# Sheet1.net
KiCad netlist of a schematic drawn in Altium Designer
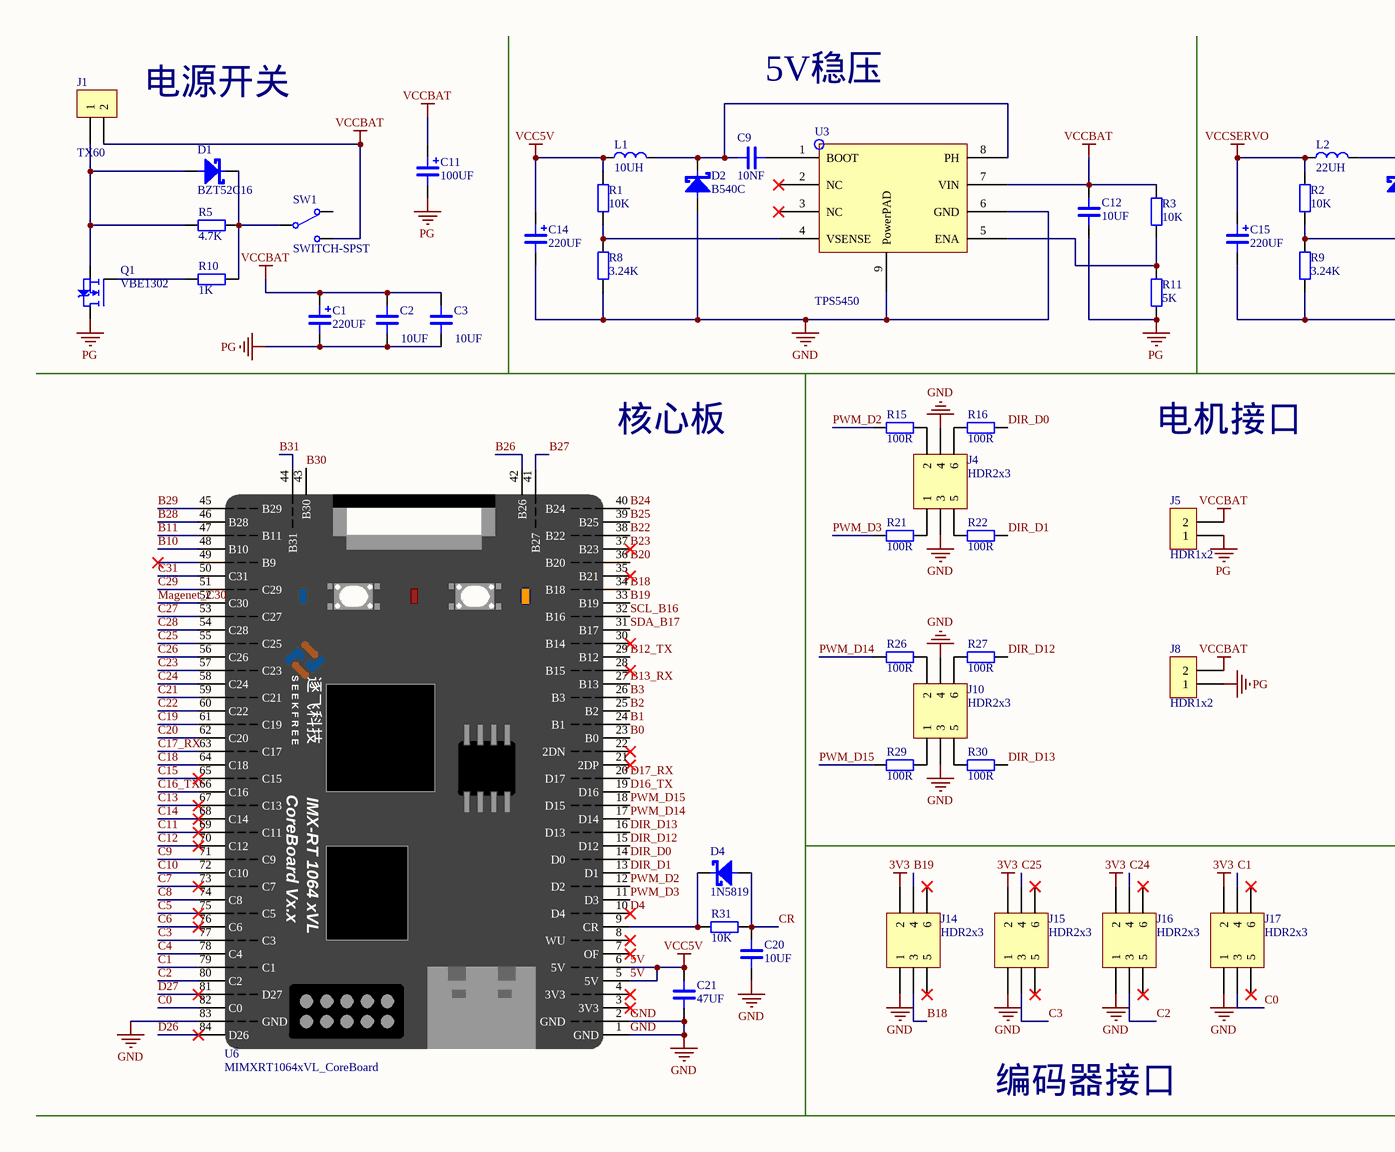
[diagram p0: Sheet1.SchDoc, left]
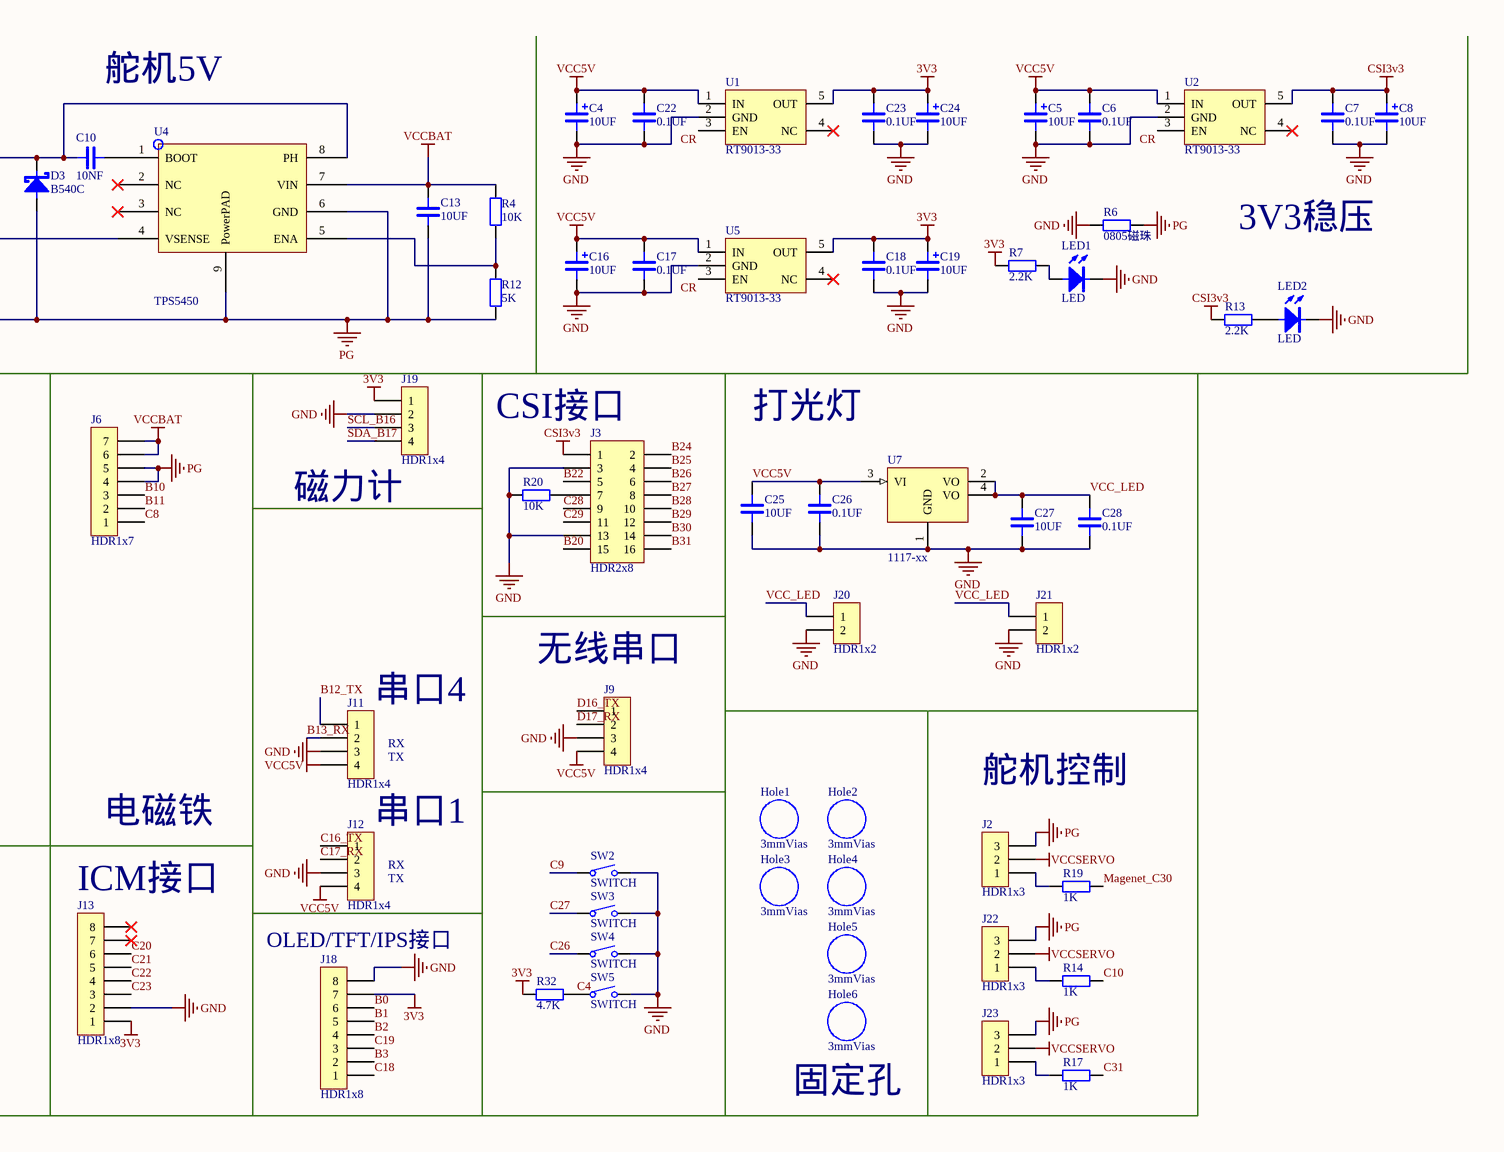
[diagram p1: Sheet1.SchDoc, right]

(export (version "E")
  (design (tool "Eeschema 10.0.6"))
  (components
    (comp (ref "C1")
      (value "220UF")
      (footprint "DIP-EC3.5X8X11.5")
      (description "Tantalum Capacitor")
      (libsource (lib "General") (part "CAP-TANTALUM"))
    )
    (comp (ref "C2")
      (value "10UF")
      (footprint "0603")
      (description "Capacitor")
      (libsource (lib "General") (part "CAP"))
    )
    (comp (ref "C3")
      (value "10UF")
      (footprint "0603")
      (description "Capacitor")
      (libsource (lib "General") (part "CAP"))
    )
    (comp (ref "C4")
      (value "10UF")
      (footprint "106")
      (description "Tantalum Capacitor")
      (libsource (lib "General") (part "CAP-TANTALUM"))
    )
    (comp (ref "C5")
      (value "10UF")
      (footprint "106")
      (description "Tantalum Capacitor")
      (libsource (lib "General") (part "CAP-TANTALUM"))
    )
    (comp (ref "C6")
      (value "0.1UF")
      (footprint "0603")
      (description "Capacitor")
      (libsource (lib "General") (part "CAP"))
    )
    (comp (ref "C7")
      (value "0.1UF")
      (footprint "0603")
      (description "Capacitor")
      (libsource (lib "General") (part "CAP"))
    )
    (comp (ref "C8")
      (value "10UF")
      (footprint "106")
      (description "Tantalum Capacitor")
      (libsource (lib "General") (part "CAP-TANTALUM"))
    )
    (comp (ref "C9")
      (value "10NF")
      (footprint "0603")
      (description "Capacitor")
      (libsource (lib "General") (part "CAP"))
    )
    (comp (ref "C10")
      (value "10NF")
      (footprint "0603")
      (description "Capacitor")
      (libsource (lib "General") (part "CAP"))
    )
    (comp (ref "C11")
      (value "100UF")
      (footprint "DIP-EC2.5X6.3X11.2")
      (description "Tantalum Capacitor")
      (libsource (lib "General") (part "CAP-TANTALUM"))
    )
    (comp (ref "C12")
      (value "10UF")
      (footprint "0603")
      (description "Capacitor")
      (libsource (lib "General") (part "CAP"))
    )
    (comp (ref "C13")
      (value "10UF")
      (footprint "0603")
      (description "Capacitor")
      (libsource (lib "General") (part "CAP"))
    )
    (comp (ref "C14")
      (value "220UF")
      (footprint "DIP-EC3.5X8X11.5")
      (description "Tantalum Capacitor")
      (libsource (lib "General") (part "CAP-TANTALUM"))
    )
    (comp (ref "C15")
      (value "220UF")
      (footprint "DIP-EC3.5X8X11.5")
      (description "Tantalum Capacitor")
      (libsource (lib "General") (part "CAP-TANTALUM"))
    )
    (comp (ref "C16")
      (value "10UF")
      (footprint "106")
      (description "Tantalum Capacitor")
      (libsource (lib "General") (part "CAP-TANTALUM"))
    )
    (comp (ref "C17")
      (value "0.1UF")
      (footprint "0603")
      (description "Capacitor")
      (libsource (lib "General") (part "CAP"))
    )
    (comp (ref "C18")
      (value "0.1UF")
      (footprint "0603")
      (description "Capacitor")
      (libsource (lib "General") (part "CAP"))
    )
    (comp (ref "C19")
      (value "10UF")
      (footprint "106")
      (description "Tantalum Capacitor")
      (libsource (lib "General") (part "CAP-TANTALUM"))
    )
    (comp (ref "C20")
      (value "10UF")
      (footprint "0603")
      (description "Capacitor")
      (libsource (lib "General") (part "CAP"))
    )
    (comp (ref "C21")
      (value "47UF")
      (footprint "1206")
      (description "Capacitor")
      (libsource (lib "General") (part "CAP"))
    )
    (comp (ref "C22")
      (value "0.1UF")
      (footprint "0603")
      (description "Capacitor")
      (libsource (lib "General") (part "CAP"))
    )
    (comp (ref "C23")
      (value "0.1UF")
      (footprint "0603")
      (description "Capacitor")
      (libsource (lib "General") (part "CAP"))
    )
    (comp (ref "C24")
      (value "10UF")
      (footprint "106")
      (description "Tantalum Capacitor")
      (libsource (lib "General") (part "CAP-TANTALUM"))
    )
    (comp (ref "C25")
      (value "10UF")
      (footprint "0603")
      (description "Capacitor")
      (libsource (lib "General") (part "CAP"))
    )
    (comp (ref "C26")
      (value "0.1UF")
      (footprint "0603")
      (description "Capacitor")
      (libsource (lib "General") (part "CAP"))
    )
    (comp (ref "C27")
      (value "10UF")
      (footprint "0603")
      (description "Capacitor")
      (libsource (lib "General") (part "CAP"))
    )
    (comp (ref "C28")
      (value "0.1UF")
      (footprint "0603")
      (description "Capacitor")
      (libsource (lib "General") (part "CAP"))
    )
    (comp (ref "D1")
      (value "BZT52C16")
      (footprint "SOD-123")
      (description "Schottky Diode")
      (libsource (lib "General") (part "SS5x"))
    )
    (comp (ref "D2")
      (value "B540C")
      (footprint "SMC")
      (description "Schottky Diode")
      (libsource (lib "General") (part "SS5x"))
    )
    (comp (ref "D3")
      (value "B540C")
      (footprint "SMC")
      (description "Schottky Diode")
      (libsource (lib "General") (part "SS5x"))
    )
    (comp (ref "D4")
      (value "1N5819")
      (footprint "SOD-123")
      (description "Schottky Diode")
      (libsource (lib "General") (part "SS5x"))
    )
    (comp (ref "Hole1") (value "3mmVias") (footprint "3mm") (libsource (lib "General") (part "3mmVias")))
    (comp (ref "Hole2") (value "3mmVias") (footprint "3mm") (libsource (lib "General") (part "3mmVias")))
    (comp (ref "Hole3") (value "3mmVias") (footprint "3mm") (libsource (lib "General") (part "3mmVias")))
    (comp (ref "Hole4") (value "3mmVias") (footprint "3mm") (libsource (lib "General") (part "3mmVias")))
    (comp (ref "Hole5") (value "3mmVias") (footprint "3mm") (libsource (lib "General") (part "3mmVias")))
    (comp (ref "Hole6") (value "3mmVias") (footprint "3mm") (libsource (lib "General") (part "3mmVias")))
    (comp (ref "J1")
      (value "TX60")
      (footprint "焊盘")
      (description "Connector")
      (libsource (lib "") (part "HDR1x2_2"))
    )
    (comp (ref "J2")
      (value "HDR1x3")
      (footprint "PIN-3-2.54-1.0")
      (description "Connector")
      (libsource (lib "General") (part "HDR1x3"))
    )
    (comp (ref "J3")
      (value "HDR2x8")
      (footprint "Fe-HDR2X8/2.54-S")
      (description "Connector")
      (libsource (lib "General") (part "HDR2x8"))
    )
    (comp (ref "J4")
      (value "HDR2x3")
      (footprint "PIN-2x3-2.54-1.0")
      (description "Connector")
      (libsource (lib "General") (part "HDR2x3"))
    )
    (comp (ref "J5")
      (value "HDR1x2")
      (footprint "TX30_焊盘")
      (description "Connector")
      (libsource (lib "General") (part "HDR1x2"))
    )
    (comp (ref "J6")
      (value "HDR1x7")
      (footprint "PIN-7-2.54-1.0")
      (description "Connector")
      (libsource (lib "General") (part "HDR1x7"))
    )
    (comp (ref "J8")
      (value "HDR1x2")
      (footprint "TX30_焊盘")
      (description "Connector")
      (libsource (lib "General") (part "HDR1x2"))
    )
    (comp (ref "J9")
      (value "HDR1x4")
      (footprint "XH4/2.54mm/180")
      (description "Connector")
      (libsource (lib "General") (part "HDR1x4"))
    )
    (comp (ref "J10")
      (value "HDR2x3")
      (footprint "PIN-2x3-2.54-1.0")
      (description "Connector")
      (libsource (lib "General") (part "HDR2x3"))
    )
    (comp (ref "J11")
      (value "HDR1x4")
      (footprint "XH4/2.54mm/180")
      (description "Connector")
      (libsource (lib "General") (part "HDR1x4"))
    )
    (comp (ref "J12")
      (value "HDR1x4")
      (footprint "XH4/2.54mm/180")
      (description "Connector")
      (libsource (lib "General") (part "HDR1x4"))
    )
    (comp (ref "J13")
      (value "HDR1x8")
      (footprint "Fe-HDR1X8/2.54-S")
      (description "Connector")
      (libsource (lib "General") (part "HDR1x8"))
    )
    (comp (ref "J14")
      (value "HDR2x3")
      (footprint "pin_2*3")
      (description "Connector")
      (libsource (lib "General") (part "HDR2x3"))
    )
    (comp (ref "J15")
      (value "HDR2x3")
      (footprint "pin_2*3")
      (description "Connector")
      (libsource (lib "General") (part "HDR2x3"))
    )
    (comp (ref "J16")
      (value "HDR2x3")
      (footprint "pin_2*3")
      (description "Connector")
      (libsource (lib "General") (part "HDR2x3"))
    )
    (comp (ref "J17")
      (value "HDR2x3")
      (footprint "pin_2*3")
      (description "Connector")
      (libsource (lib "General") (part "HDR2x3"))
    )
    (comp (ref "J18")
      (value "HDR1x8")
      (footprint "Fe-HDR1X8/2.54-S")
      (description "Connector")
      (libsource (lib "General") (part "HDR1x8"))
    )
    (comp (ref "J19")
      (value "HDR1x4")
      (footprint "PIN-4-2.54-1.0")
      (description "Connector")
      (libsource (lib "General") (part "HDR1x4"))
    )
    (comp (ref "J20")
      (value "HDR1x2")
      (footprint "PIN-2-2.54-1.0")
      (description "Connector")
      (libsource (lib "") (part "HDR1x2_1"))
    )
    (comp (ref "J21")
      (value "HDR1x2")
      (footprint "PIN-2-2.54-1.0")
      (description "Connector")
      (libsource (lib "") (part "HDR1x2_1"))
    )
    (comp (ref "J22")
      (value "HDR1x3")
      (footprint "PIN-3-2.54-1.0")
      (description "Connector")
      (libsource (lib "General") (part "HDR1x3"))
    )
    (comp (ref "J23")
      (value "HDR1x3")
      (footprint "PIN-3-2.54-1.0")
      (description "Connector")
      (libsource (lib "General") (part "HDR1x3"))
    )
    (comp (ref "L1")
      (value "10UH")
      (footprint "CDRH73")
      (description "Inductance")
      (libsource (lib "General") (part "INDUCTANCE"))
    )
    (comp (ref "L2")
      (value "22UH")
      (footprint "CDRH73")
      (description "Inductance")
      (libsource (lib "General") (part "INDUCTANCE"))
    )
    (comp (ref "LED1") (value "LED") (footprint "0603-led") (libsource (lib "General") (part "LED")))
    (comp (ref "LED2") (value "LED") (footprint "0603-led") (libsource (lib "General") (part "LED")))
    (comp (ref "Q1")
      (value "VBE1302")
      (footprint "TO252")
      (description "N-Channel MOSFET")
      (libsource (lib "General") (part "FDB52N20"))
    )
    (comp (ref "R1")
      (value "10K")
      (footprint "0603")
      (description "Resistor")
      (libsource (lib "") (part "RES_1"))
    )
    (comp (ref "R2")
      (value "10K")
      (footprint "0603")
      (description "Resistor")
      (libsource (lib "") (part "RES_1"))
    )
    (comp (ref "R3")
      (value "10K")
      (footprint "0603")
      (description "Resistor")
      (libsource (lib "") (part "RES_1"))
    )
    (comp (ref "R4")
      (value "10K")
      (footprint "0603")
      (description "Resistor")
      (libsource (lib "") (part "RES_1"))
    )
    (comp (ref "R5")
      (value "4.7K")
      (footprint "0603")
      (description "Resistor")
      (libsource (lib "") (part "RES_2"))
    )
    (comp (ref "R6")
      (value "0805磁珠")
      (footprint "0805")
      (description "Resistor")
      (libsource (lib "General") (part "RES"))
    )
    (comp (ref "R7")
      (value "2.2K")
      (footprint "0603")
      (description "Resistor")
      (libsource (lib "General") (part "RES"))
    )
    (comp (ref "R8")
      (value "3.24K")
      (footprint "0603")
      (description "Resistor")
      (libsource (lib "") (part "RES_1"))
    )
    (comp (ref "R9")
      (value "3.24K")
      (footprint "0603")
      (description "Resistor")
      (libsource (lib "") (part "RES_1"))
    )
    (comp (ref "R10")
      (value "1K")
      (footprint "0603")
      (description "Resistor")
      (libsource (lib "") (part "RES_2"))
    )
    (comp (ref "R11")
      (value "5K")
      (footprint "0603")
      (description "Resistor")
      (libsource (lib "") (part "RES_1"))
    )
    (comp (ref "R12")
      (value "5K")
      (footprint "0603")
      (description "Resistor")
      (libsource (lib "") (part "RES_1"))
    )
    (comp (ref "R13")
      (value "2.2K")
      (footprint "0603")
      (description "Resistor")
      (libsource (lib "General") (part "RES"))
    )
    (comp (ref "R14")
      (value "1K")
      (footprint "0603")
      (description "Resistor")
      (libsource (lib "") (part "RES_2"))
    )
    (comp (ref "R15")
      (value "100R")
      (footprint "0603")
      (description "Resistor")
      (libsource (lib "") (part "RES_2"))
    )
    (comp (ref "R16")
      (value "100R")
      (footprint "0603")
      (description "Resistor")
      (libsource (lib "General") (part "RES"))
    )
    (comp (ref "R17")
      (value "1K")
      (footprint "0603")
      (description "Resistor")
      (libsource (lib "") (part "RES_2"))
    )
    (comp (ref "R19")
      (value "1K")
      (footprint "0603")
      (description "Resistor")
      (libsource (lib "") (part "RES_2"))
    )
    (comp (ref "R20")
      (value "10K")
      (footprint "0603")
      (description "Resistor")
      (libsource (lib "General") (part "RES"))
    )
    (comp (ref "R21")
      (value "100R")
      (footprint "0603")
      (description "Resistor")
      (libsource (lib "General") (part "RES"))
    )
    (comp (ref "R22")
      (value "100R")
      (footprint "0603")
      (description "Resistor")
      (libsource (lib "General") (part "RES"))
    )
    (comp (ref "R26")
      (value "100R")
      (footprint "0603")
      (description "Resistor")
      (libsource (lib "General") (part "RES"))
    )
    (comp (ref "R27")
      (value "100R")
      (footprint "0603")
      (description "Resistor")
      (libsource (lib "General") (part "RES"))
    )
    (comp (ref "R29")
      (value "100R")
      (footprint "0603")
      (description "Resistor")
      (libsource (lib "General") (part "RES"))
    )
    (comp (ref "R30")
      (value "100R")
      (footprint "0603")
      (description "Resistor")
      (libsource (lib "General") (part "RES"))
    )
    (comp (ref "R31")
      (value "10K")
      (footprint "0603")
      (description "Resistor")
      (libsource (lib "General") (part "RES"))
    )
    (comp (ref "R32")
      (value "4.7K")
      (footprint "0603")
      (description "Resistor")
      (libsource (lib "") (part "RES_2"))
    )
    (comp (ref "SW1")
      (value "SWITCH-SPST")
      (footprint "ss12d10")
      (description "Switch")
      (libsource (lib "General") (part "SWITCH-SPST"))
    )
    (comp (ref "SW2")
      (value "SWITCH")
      (footprint "按键")
      (description "Switch")
      (libsource (lib "General") (part "SWITCH"))
    )
    (comp (ref "SW3")
      (value "SWITCH")
      (footprint "按键")
      (description "Switch")
      (libsource (lib "General") (part "SWITCH"))
    )
    (comp (ref "SW4")
      (value "SWITCH")
      (footprint "按键")
      (description "Switch")
      (libsource (lib "General") (part "SWITCH"))
    )
    (comp (ref "SW5")
      (value "SWITCH")
      (footprint "按键")
      (description "Switch")
      (libsource (lib "General") (part "SWITCH"))
    )
    (comp (ref "U1")
      (value "RT9013-33")
      (footprint "RT9013-33")
      (description "3.3V 500mA SOT23-5 LDO")
      (libsource (lib "TC264主板") (part "RT9013-33"))
    )
    (comp (ref "U2")
      (value "RT9013-33")
      (footprint "RT9013-33")
      (description "3.3V 500mA SOT23-5 LDO")
      (libsource (lib "TC264主板") (part "RT9013-33"))
    )
    (comp (ref "U3") (value "TPS5450") (footprint "TPS5450") (libsource (lib "General") (part "TPS5450")))
    (comp (ref "U4") (value "TPS5450") (footprint "TPS5450") (libsource (lib "General") (part "TPS5450")))
    (comp (ref "U5")
      (value "RT9013-33")
      (footprint "RT9013-33")
      (description "3.3V 500mA SOT23-5 LDO")
      (libsource (lib "TC264主板") (part "RT9013-33"))
    )
    (comp (ref "U6")
      (value "MIMXRT1064xVL_CoreBoard")
      (footprint "MIMXRT1064xVL_CoreBoard")
      (description "逐飞科技i.MX RT1064核心板整体原理，可直接使用")
      (libsource (lib "RT1064 核心板原理库") (part "MIMXRT1064xVL_CoreBoard"))
    )
    (comp (ref "U7")
      (value "1117-xx")
      (footprint "SOT223_4")
      (description "Linear Regulator")
      (libsource (lib "General") (part "1117"))
    )
  )
  (nets
    (net (code "1") (name "/B0") (class "Default")
      (node (ref "J18") (pin "6") (pinfunction "6_6") (pintype "passive"))
      (node (ref "U6") (pin "23") (pinfunction "B0_23") (pintype "passive"))
    )
    (net (code "2") (name "/B1") (class "Default")
      (node (ref "J18") (pin "5") (pinfunction "5_5") (pintype "passive"))
      (node (ref "U6") (pin "24") (pinfunction "B1_24") (pintype "passive"))
    )
    (net (code "3") (name "/B2") (class "Default")
      (node (ref "J18") (pin "4") (pinfunction "4_4") (pintype "passive"))
      (node (ref "U6") (pin "25") (pinfunction "B2_25") (pintype "passive"))
    )
    (net (code "4") (name "/B3") (class "Default")
      (node (ref "J18") (pin "2") (pinfunction "2_2") (pintype "passive"))
      (node (ref "U6") (pin "26") (pinfunction "B3_26") (pintype "passive"))
    )
    (net (code "5") (name "/B10") (class "Default")
      (node (ref "J6") (pin "3") (pinfunction "3_3") (pintype "passive"))
      (node (ref "U6") (pin "48") (pinfunction "B10_48") (pintype "passive"))
    )
    (net (code "6") (name "/B11") (class "Default")
      (node (ref "J6") (pin "2") (pinfunction "2_2") (pintype "passive"))
      (node (ref "U6") (pin "47") (pinfunction "B11_47") (pintype "passive"))
    )
    (net (code "7") (name "/B12_TX") (class "Default")
      (node (ref "J11") (pin "1") (pinfunction "1_1") (pintype "passive"))
      (node (ref "U6") (pin "29") (pinfunction "B12_29") (pintype "passive"))
    )
    (net (code "8") (name "/B13_RX") (class "Default")
      (node (ref "J11") (pin "2") (pinfunction "2_2") (pintype "passive"))
      (node (ref "U6") (pin "27") (pinfunction "B13_27") (pintype "passive"))
    )
    (net (code "9") (name "/B18") (class "Default")
      (node (ref "J14") (pin "3") (pinfunction "3_3") (pintype "passive"))
      (node (ref "U6") (pin "34") (pinfunction "B18_34") (pintype "passive"))
    )
    (net (code "10") (name "/B19") (class "Default")
      (node (ref "J14") (pin "4") (pinfunction "4_4") (pintype "passive"))
      (node (ref "U6") (pin "33") (pinfunction "B19_33") (pintype "passive"))
    )
    (net (code "11") (name "/B20") (class "Default")
      (node (ref "J3") (pin "15") (pinfunction "15_15") (pintype "passive"))
      (node (ref "U6") (pin "36") (pinfunction "B20_36") (pintype "passive"))
    )
    (net (code "12") (name "/B22") (class "Default")
      (node (ref "J3") (pin "5") (pinfunction "5_5") (pintype "passive"))
      (node (ref "U6") (pin "38") (pinfunction "B22_38") (pintype "passive"))
    )
    (net (code "13") (name "/B23") (class "Default")
      (node (ref "U6") (pin "37") (pinfunction "B23_37") (pintype "passive+no_connect"))
    )
    (net (code "14") (name "/B24") (class "Default")
      (node (ref "J3") (pin "2") (pinfunction "2_2") (pintype "passive"))
      (node (ref "U6") (pin "40") (pinfunction "B24_40") (pintype "passive"))
    )
    (net (code "15") (name "/B25") (class "Default")
      (node (ref "J3") (pin "4") (pinfunction "4_4") (pintype "passive"))
      (node (ref "U6") (pin "39") (pinfunction "B25_39") (pintype "passive"))
    )
    (net (code "16") (name "/B26") (class "Default")
      (node (ref "J3") (pin "6") (pinfunction "6_6") (pintype "passive"))
      (node (ref "U6") (pin "42") (pinfunction "B26_42") (pintype "passive"))
    )
    (net (code "17") (name "/B27") (class "Default")
      (node (ref "J3") (pin "8") (pinfunction "8_8") (pintype "passive"))
      (node (ref "U6") (pin "41") (pinfunction "B27_41") (pintype "passive"))
    )
    (net (code "18") (name "/B28") (class "Default")
      (node (ref "J3") (pin "10") (pinfunction "10_10") (pintype "passive"))
      (node (ref "U6") (pin "46") (pinfunction "B28_46") (pintype "passive"))
    )
    (net (code "19") (name "/B29") (class "Default")
      (node (ref "J3") (pin "12") (pinfunction "12_12") (pintype "passive"))
      (node (ref "U6") (pin "45") (pinfunction "B29_45") (pintype "passive"))
    )
    (net (code "20") (name "/B30") (class "Default")
      (node (ref "J3") (pin "14") (pinfunction "14_14") (pintype "passive"))
      (node (ref "U6") (pin "43") (pinfunction "B30_43") (pintype "passive"))
    )
    (net (code "21") (name "/B31") (class "Default")
      (node (ref "J3") (pin "16") (pinfunction "16_16") (pintype "passive"))
      (node (ref "U6") (pin "44") (pinfunction "B31_44") (pintype "passive"))
    )
    (net (code "22") (name "/C0") (class "Default")
      (node (ref "J17") (pin "3") (pinfunction "3_3") (pintype "passive"))
      (node (ref "U6") (pin "82") (pinfunction "C0_82") (pintype "passive"))
    )
    (net (code "23") (name "/C1") (class "Default")
      (node (ref "J17") (pin "4") (pinfunction "4_4") (pintype "passive"))
      (node (ref "U6") (pin "79") (pinfunction "C1_79") (pintype "passive"))
    )
    (net (code "24") (name "/C2") (class "Default")
      (node (ref "J16") (pin "3") (pinfunction "3_3") (pintype "passive"))
      (node (ref "U6") (pin "80") (pinfunction "C2_80") (pintype "passive"))
    )
    (net (code "25") (name "/C3") (class "Default")
      (node (ref "J15") (pin "3") (pinfunction "3_3") (pintype "passive"))
      (node (ref "U6") (pin "77") (pinfunction "C3_77") (pintype "passive"))
    )
    (net (code "26") (name "/C4") (class "Default")
      (node (ref "R32") (pin "2") (pinfunction "2_2") (pintype "passive"))
      (node (ref "SW5") (pin "1") (pinfunction "1_1") (pintype "passive"))
      (node (ref "U6") (pin "78") (pinfunction "C4_78") (pintype "passive"))
    )
    (net (code "27") (name "/C5") (class "Default")
      (node (ref "U6") (pin "75") (pinfunction "C5_75") (pintype "passive+no_connect"))
    )
    (net (code "28") (name "/C6") (class "Default")
      (node (ref "U6") (pin "76") (pinfunction "C6_76") (pintype "passive+no_connect"))
    )
    (net (code "29") (name "/C7") (class "Default")
      (node (ref "U6") (pin "73") (pinfunction "C7_73") (pintype "passive+no_connect"))
    )
    (net (code "30") (name "/C8") (class "Default")
      (node (ref "J6") (pin "1") (pinfunction "1_1") (pintype "passive"))
      (node (ref "U6") (pin "74") (pinfunction "C8_74") (pintype "passive"))
    )
    (net (code "31") (name "/C9") (class "Default")
      (node (ref "SW2") (pin "1") (pinfunction "1_1") (pintype "passive"))
      (node (ref "U6") (pin "71") (pinfunction "C9_71") (pintype "passive"))
    )
    (net (code "32") (name "/C10") (class "Default")
      (node (ref "R14") (pin "2") (pinfunction "2_2") (pintype "passive"))
      (node (ref "U6") (pin "72") (pinfunction "C10_72") (pintype "passive"))
    )
    (net (code "33") (name "/C11") (class "Default")
      (node (ref "U6") (pin "69") (pinfunction "C11_69") (pintype "passive+no_connect"))
    )
    (net (code "34") (name "/C12") (class "Default")
      (node (ref "U6") (pin "70") (pinfunction "C12_70") (pintype "passive+no_connect"))
    )
    (net (code "35") (name "/C13") (class "Default")
      (node (ref "U6") (pin "67") (pinfunction "C13_67") (pintype "passive+no_connect"))
    )
    (net (code "36") (name "/C14") (class "Default")
      (node (ref "U6") (pin "68") (pinfunction "C14_68") (pintype "passive+no_connect"))
    )
    (net (code "37") (name "/C15") (class "Default")
      (node (ref "U6") (pin "65") (pinfunction "C15_65") (pintype "passive+no_connect"))
    )
    (net (code "38") (name "/C16_TX") (class "Default")
      (node (ref "J12") (pin "1") (pinfunction "1_1") (pintype "passive"))
      (node (ref "U6") (pin "66") (pinfunction "C16_66") (pintype "passive"))
    )
    (net (code "39") (name "/C17_RX") (class "Default")
      (node (ref "J12") (pin "2") (pinfunction "2_2") (pintype "passive"))
      (node (ref "U6") (pin "63") (pinfunction "C17_63") (pintype "passive"))
    )
    (net (code "40") (name "/C18") (class "Default")
      (node (ref "J18") (pin "1") (pinfunction "1_1") (pintype "passive"))
      (node (ref "U6") (pin "64") (pinfunction "C18_64") (pintype "passive"))
    )
    (net (code "41") (name "/C19") (class "Default")
      (node (ref "J18") (pin "3") (pinfunction "3_3") (pintype "passive"))
      (node (ref "U6") (pin "61") (pinfunction "C19_61") (pintype "passive"))
    )
    (net (code "42") (name "/C20") (class "Default")
      (node (ref "J13") (pin "6") (pinfunction "6_6") (pintype "passive"))
      (node (ref "U6") (pin "62") (pinfunction "C20_62") (pintype "passive"))
    )
    (net (code "43") (name "/C21") (class "Default")
      (node (ref "J13") (pin "5") (pinfunction "5_5") (pintype "passive"))
      (node (ref "U6") (pin "59") (pinfunction "C21_59") (pintype "passive"))
    )
    (net (code "44") (name "/C22") (class "Default")
      (node (ref "J13") (pin "4") (pinfunction "4_4") (pintype "passive"))
      (node (ref "U6") (pin "60") (pinfunction "C22_60") (pintype "passive"))
    )
    (net (code "45") (name "/C23") (class "Default")
      (node (ref "J13") (pin "3") (pinfunction "3_3") (pintype "passive"))
      (node (ref "U6") (pin "57") (pinfunction "C23_57") (pintype "passive"))
    )
    (net (code "46") (name "/C24") (class "Default")
      (node (ref "J16") (pin "4") (pinfunction "4_4") (pintype "passive"))
      (node (ref "U6") (pin "58") (pinfunction "C24_58") (pintype "passive"))
    )
    (net (code "47") (name "/C25") (class "Default")
      (node (ref "J15") (pin "4") (pinfunction "4_4") (pintype "passive"))
      (node (ref "U6") (pin "55") (pinfunction "C25_55") (pintype "passive"))
    )
    (net (code "48") (name "/C26") (class "Default")
      (node (ref "SW4") (pin "1") (pinfunction "1_1") (pintype "passive"))
      (node (ref "U6") (pin "56") (pinfunction "C26_56") (pintype "passive"))
    )
    (net (code "49") (name "/C27") (class "Default")
      (node (ref "SW3") (pin "1") (pinfunction "1_1") (pintype "passive"))
      (node (ref "U6") (pin "53") (pinfunction "C27_53") (pintype "passive"))
    )
    (net (code "50") (name "/C28") (class "Default")
      (node (ref "J3") (pin "9") (pinfunction "9_9") (pintype "passive"))
      (node (ref "U6") (pin "54") (pinfunction "C28_54") (pintype "passive"))
    )
    (net (code "51") (name "/C29") (class "Default")
      (node (ref "J3") (pin "11") (pinfunction "11_11") (pintype "passive"))
      (node (ref "U6") (pin "51") (pinfunction "C29_51") (pintype "passive"))
    )
    (net (code "52") (name "/C31") (class "Default")
      (node (ref "R17") (pin "2") (pinfunction "2_2") (pintype "passive"))
      (node (ref "U6") (pin "50") (pinfunction "C31_50") (pintype "passive"))
    )
    (net (code "53") (name "/CR") (class "Default")
      (node (ref "C20") (pin "2") (pinfunction "2_2") (pintype "passive"))
      (node (ref "D4") (pin "1") (pinfunction "A_1") (pintype "passive"))
      (node (ref "R31") (pin "1") (pinfunction "1_1") (pintype "passive"))
      (node (ref "U1") (pin "3") (pinfunction "EN_3") (pintype "passive"))
      (node (ref "U2") (pin "3") (pinfunction "EN_3") (pintype "passive"))
      (node (ref "U5") (pin "3") (pinfunction "EN_3") (pintype "passive"))
    )
    (net (code "54") (name "/D4") (class "Default")
      (node (ref "U6") (pin "10") (pinfunction "D4_10") (pintype "passive+no_connect"))
    )
    (net (code "55") (name "/D16_TX") (class "Default")
      (node (ref "J9") (pin "1") (pinfunction "1_1") (pintype "passive"))
      (node (ref "U6") (pin "19") (pinfunction "D16_19") (pintype "passive"))
    )
    (net (code "56") (name "/D17_RX") (class "Default")
      (node (ref "J9") (pin "2") (pinfunction "2_2") (pintype "passive"))
      (node (ref "U6") (pin "20") (pinfunction "D17_20") (pintype "passive"))
    )
    (net (code "57") (name "/D26") (class "Default")
      (node (ref "U6") (pin "84") (pinfunction "D26_84") (pintype "passive+no_connect"))
    )
    (net (code "58") (name "/D27") (class "Default")
      (node (ref "U6") (pin "81") (pinfunction "D27_81") (pintype "passive+no_connect"))
    )
    (net (code "59") (name "/DIR_D0") (class "Default")
      (node (ref "R16") (pin "1") (pinfunction "1_1") (pintype "passive"))
      (node (ref "U6") (pin "14") (pinfunction "D0_14") (pintype "passive"))
    )
    (net (code "60") (name "/DIR_D1") (class "Default")
      (node (ref "R22") (pin "1") (pinfunction "1_1") (pintype "passive"))
      (node (ref "U6") (pin "13") (pinfunction "D1_13") (pintype "passive"))
    )
    (net (code "61") (name "/DIR_D12") (class "Default")
      (node (ref "R27") (pin "1") (pinfunction "1_1") (pintype "passive"))
      (node (ref "U6") (pin "15") (pinfunction "D12_15") (pintype "passive"))
    )
    (net (code "62") (name "/DIR_D13") (class "Default")
      (node (ref "R30") (pin "1") (pinfunction "1_1") (pintype "passive"))
      (node (ref "U6") (pin "16") (pinfunction "D13_16") (pintype "passive"))
    )
    (net (code "63") (name "/Magenet_C30") (class "Default")
      (node (ref "R19") (pin "2") (pinfunction "2_2") (pintype "passive"))
      (node (ref "U6") (pin "52") (pinfunction "C30_52") (pintype "passive"))
    )
    (net (code "64") (name "/PWM_D2") (class "Default")
      (node (ref "R15") (pin "1") (pinfunction "1_1") (pintype "passive"))
      (node (ref "U6") (pin "12") (pinfunction "D2_12") (pintype "passive"))
    )
    (net (code "65") (name "/PWM_D3") (class "Default")
      (node (ref "R21") (pin "2") (pinfunction "2_2") (pintype "passive"))
      (node (ref "U6") (pin "11") (pinfunction "D3_11") (pintype "passive"))
    )
    (net (code "66") (name "/PWM_D14") (class "Default")
      (node (ref "R26") (pin "2") (pinfunction "2_2") (pintype "passive"))
      (node (ref "U6") (pin "17") (pinfunction "D14_17") (pintype "passive"))
    )
    (net (code "67") (name "/PWM_D15") (class "Default")
      (node (ref "R29") (pin "2") (pinfunction "2_2") (pintype "passive"))
      (node (ref "U6") (pin "18") (pinfunction "D15_18") (pintype "passive"))
    )
    (net (code "68") (name "/SCL_B16") (class "Default")
      (node (ref "J19") (pin "3") (pinfunction "3_3") (pintype "passive"))
      (node (ref "U6") (pin "32") (pinfunction "B16_32") (pintype "passive"))
    )
    (net (code "69") (name "/SDA_B17") (class "Default")
      (node (ref "J19") (pin "4") (pinfunction "4_4") (pintype "passive"))
      (node (ref "U6") (pin "31") (pinfunction "B17_31") (pintype "passive"))
    )
    (net (code "70") (name "/VCC_LED") (class "Default")
      (node (ref "C27") (pin "1") (pinfunction "1_1") (pintype "passive"))
      (node (ref "C28") (pin "1") (pinfunction "1_1") (pintype "passive"))
      (node (ref "J20") (pin "1") (pinfunction "1_1") (pintype "passive"))
      (node (ref "J21") (pin "1") (pinfunction "1_1") (pintype "passive"))
      (node (ref "U7") (pin "2") (pinfunction "VO_2") (pintype "power_in"))
      (node (ref "U7") (pin "4") (pinfunction "VO_4") (pintype "power_in"))
    )
    (net (code "71") (name "3V3") (class "Default")
      (node (ref "C18") (pin "1") (pinfunction "1_1") (pintype "passive"))
      (node (ref "C19") (pin "1") (pinfunction "1_1") (pintype "passive"))
      (node (ref "C23") (pin "1") (pinfunction "1_1") (pintype "passive"))
      (node (ref "C24") (pin "1") (pinfunction "1_1") (pintype "passive"))
      (node (ref "J13") (pin "1") (pinfunction "1_1") (pintype "passive"))
      (node (ref "J14") (pin "2") (pinfunction "2_2") (pintype "passive"))
      (node (ref "J15") (pin "2") (pinfunction "2_2") (pintype "passive"))
      (node (ref "J16") (pin "2") (pinfunction "2_2") (pintype "passive"))
      (node (ref "J17") (pin "2") (pinfunction "2_2") (pintype "passive"))
      (node (ref "J18") (pin "7") (pinfunction "7_7") (pintype "passive"))
      (node (ref "J19") (pin "1") (pinfunction "1_1") (pintype "passive"))
      (node (ref "R32") (pin "1") (pinfunction "1_1") (pintype "passive"))
      (node (ref "R7") (pin "2") (pinfunction "2_2") (pintype "passive"))
      (node (ref "U1") (pin "5") (pinfunction "OUT_5") (pintype "passive"))
      (node (ref "U5") (pin "5") (pinfunction "OUT_5") (pintype "passive"))
    )
    (net (code "72") (name "CSI3v3") (class "Default")
      (node (ref "C7") (pin "1") (pinfunction "1_1") (pintype "passive"))
      (node (ref "C8") (pin "1") (pinfunction "1_1") (pintype "passive"))
      (node (ref "J3") (pin "1") (pinfunction "1_1") (pintype "passive"))
      (node (ref "R13") (pin "2") (pinfunction "2_2") (pintype "passive"))
      (node (ref "U2") (pin "5") (pinfunction "OUT_5") (pintype "passive"))
    )
    (net (code "73") (name "GND") (class "Default")
      (node (ref "C14") (pin "2") (pinfunction "2_2") (pintype "passive"))
      (node (ref "C16") (pin "2") (pinfunction "2_2") (pintype "passive"))
      (node (ref "C17") (pin "2") (pinfunction "2_2") (pintype "passive"))
      (node (ref "C18") (pin "2") (pinfunction "2_2") (pintype "passive"))
      (node (ref "C19") (pin "2") (pinfunction "2_2") (pintype "passive"))
      (node (ref "C20") (pin "1") (pinfunction "1_1") (pintype "passive"))
      (node (ref "C21") (pin "1") (pinfunction "1_1") (pintype "passive"))
      (node (ref "C22") (pin "2") (pinfunction "2_2") (pintype "passive"))
      (node (ref "C23") (pin "2") (pinfunction "2_2") (pintype "passive"))
      (node (ref "C24") (pin "2") (pinfunction "2_2") (pintype "passive"))
      (node (ref "C25") (pin "2") (pinfunction "2_2") (pintype "passive"))
      (node (ref "C26") (pin "2") (pinfunction "2_2") (pintype "passive"))
      (node (ref "C27") (pin "2") (pinfunction "2_2") (pintype "passive"))
      (node (ref "C28") (pin "2") (pinfunction "2_2") (pintype "passive"))
      (node (ref "C4") (pin "2") (pinfunction "2_2") (pintype "passive"))
      (node (ref "C5") (pin "2") (pinfunction "2_2") (pintype "passive"))
      (node (ref "C6") (pin "2") (pinfunction "2_2") (pintype "passive"))
      (node (ref "C7") (pin "2") (pinfunction "2_2") (pintype "passive"))
      (node (ref "C8") (pin "2") (pinfunction "2_2") (pintype "passive"))
      (node (ref "D2") (pin "1") (pinfunction "A_1") (pintype "passive"))
      (node (ref "J10") (pin "3") (pinfunction "3_3") (pintype "passive"))
      (node (ref "J10") (pin "4") (pinfunction "4_4") (pintype "passive"))
      (node (ref "J11") (pin "3") (pinfunction "3_3") (pintype "passive"))
      (node (ref "J12") (pin "3") (pinfunction "3_3") (pintype "passive"))
      (node (ref "J13") (pin "2") (pinfunction "2_2") (pintype "passive"))
      (node (ref "J14") (pin "1") (pinfunction "1_1") (pintype "passive"))
      (node (ref "J15") (pin "1") (pinfunction "1_1") (pintype "passive"))
      (node (ref "J16") (pin "1") (pinfunction "1_1") (pintype "passive"))
      (node (ref "J17") (pin "1") (pinfunction "1_1") (pintype "passive"))
      (node (ref "J18") (pin "8") (pinfunction "8_8") (pintype "passive"))
      (node (ref "J19") (pin "2") (pinfunction "2_2") (pintype "passive"))
      (node (ref "J20") (pin "2") (pinfunction "2_2") (pintype "passive"))
      (node (ref "J21") (pin "2") (pinfunction "2_2") (pintype "passive"))
      (node (ref "J3") (pin "13") (pinfunction "13_13") (pintype "passive"))
      (node (ref "J3") (pin "3") (pinfunction "3_3") (pintype "passive"))
      (node (ref "J4") (pin "3") (pinfunction "3_3") (pintype "passive"))
      (node (ref "J4") (pin "4") (pinfunction "4_4") (pintype "passive"))
      (node (ref "J9") (pin "3") (pinfunction "3_3") (pintype "passive"))
      (node (ref "LED1") (pin "2") (pinfunction "C_2") (pintype "passive"))
      (node (ref "LED2") (pin "2") (pinfunction "C_2") (pintype "passive"))
      (node (ref "R20") (pin "2") (pinfunction "2_2") (pintype "passive"))
      (node (ref "R6") (pin "2") (pinfunction "2_2") (pintype "passive"))
      (node (ref "R8") (pin "1") (pinfunction "1_1") (pintype "passive"))
      (node (ref "SW2") (pin "2") (pinfunction "2_2") (pintype "passive"))
      (node (ref "SW3") (pin "2") (pinfunction "2_2") (pintype "passive"))
      (node (ref "SW4") (pin "2") (pinfunction "2_2") (pintype "passive"))
      (node (ref "SW5") (pin "2") (pinfunction "2_2") (pintype "passive"))
      (node (ref "U1") (pin "2") (pinfunction "GND_2") (pintype "passive"))
      (node (ref "U2") (pin "2") (pinfunction "GND_2") (pintype "passive"))
      (node (ref "U3") (pin "6") (pinfunction "GND_6") (pintype "passive"))
      (node (ref "U3") (pin "9") (pinfunction "PowerPAD_9") (pintype "passive"))
      (node (ref "U5") (pin "2") (pinfunction "GND_2") (pintype "passive"))
      (node (ref "U6") (pin "1") (pinfunction "GND_1") (pintype "passive"))
      (node (ref "U6") (pin "2") (pinfunction "GND_2") (pintype "passive"))
      (node (ref "U6") (pin "83") (pinfunction "GND_83") (pintype "passive"))
      (node (ref "U7") (pin "1") (pinfunction "GND_1") (pintype "power_in"))
    )
    (net (code "74") (name "Net-(D1-A)") (class "Default")
      (node (ref "D1") (pin "1") (pinfunction "A_1") (pintype "passive"))
      (node (ref "J1") (pin "1") (pinfunction "1_1") (pintype "passive"))
      (node (ref "Q1") (pin "3") (pinfunction "S_3") (pintype "passive"))
      (node (ref "R5") (pin "1") (pinfunction "1_1") (pintype "passive"))
    )
    (net (code "75") (name "Net-(D1-C)") (class "Default")
      (node (ref "D1") (pin "2") (pinfunction "C_2") (pintype "passive"))
      (node (ref "R10") (pin "2") (pinfunction "2_2") (pintype "passive"))
      (node (ref "R5") (pin "2") (pinfunction "2_2") (pintype "passive"))
      (node (ref "SW1") (pin "2") (pinfunction "2_2") (pintype "passive"))
    )
    (net (code "76") (name "Net-(D2-C)") (class "Default")
      (node (ref "C9") (pin "2") (pinfunction "2_2") (pintype "passive"))
      (node (ref "D2") (pin "2") (pinfunction "C_2") (pintype "passive"))
      (node (ref "L1") (pin "2") (pinfunction "2_2") (pintype "passive"))
      (node (ref "U3") (pin "8") (pinfunction "PH_8") (pintype "passive"))
    )
    (net (code "77") (name "Net-(D3-C)") (class "Default")
      (node (ref "C10") (pin "2") (pinfunction "2_2") (pintype "passive"))
      (node (ref "D3") (pin "2") (pinfunction "C_2") (pintype "passive"))
      (node (ref "L2") (pin "2") (pinfunction "2_2") (pintype "passive"))
      (node (ref "U4") (pin "8") (pinfunction "PH_8") (pintype "passive"))
    )
    (net (code "78") (name "Net-(D4-C)") (class "Default")
      (node (ref "D4") (pin "2") (pinfunction "C_2") (pintype "passive"))
      (node (ref "R31") (pin "2") (pinfunction "2_2") (pintype "passive"))
      (node (ref "U6") (pin "9") (pinfunction "CR_9") (pintype "passive"))
    )
    (net (code "79") (name "Net-(J2-Pad1)") (class "Default")
      (node (ref "J2") (pin "1") (pinfunction "1_1") (pintype "passive"))
      (node (ref "R19") (pin "1") (pinfunction "1_1") (pintype "passive"))
    )
    (net (code "80") (name "Net-(J3-Pad7)") (class "Default")
      (node (ref "J3") (pin "7") (pinfunction "7_7") (pintype "passive"))
      (node (ref "R20") (pin "1") (pinfunction "1_1") (pintype "passive"))
    )
    (net (code "81") (name "Net-(J4-Pad1)") (class "Default")
      (node (ref "J4") (pin "1") (pinfunction "1_1") (pintype "passive"))
      (node (ref "R21") (pin "1") (pinfunction "1_1") (pintype "passive"))
    )
    (net (code "82") (name "Net-(J4-Pad2)") (class "Default")
      (node (ref "J4") (pin "2") (pinfunction "2_2") (pintype "passive"))
      (node (ref "R15") (pin "2") (pinfunction "2_2") (pintype "passive"))
    )
    (net (code "83") (name "Net-(J4-Pad5)") (class "Default")
      (node (ref "J4") (pin "5") (pinfunction "5_5") (pintype "passive"))
      (node (ref "R22") (pin "2") (pinfunction "2_2") (pintype "passive"))
    )
    (net (code "84") (name "Net-(J4-Pad6)") (class "Default")
      (node (ref "J4") (pin "6") (pinfunction "6_6") (pintype "passive"))
      (node (ref "R16") (pin "2") (pinfunction "2_2") (pintype "passive"))
    )
    (net (code "85") (name "Net-(J10-Pad1)") (class "Default")
      (node (ref "J10") (pin "1") (pinfunction "1_1") (pintype "passive"))
      (node (ref "R29") (pin "1") (pinfunction "1_1") (pintype "passive"))
    )
    (net (code "86") (name "Net-(J10-Pad2)") (class "Default")
      (node (ref "J10") (pin "2") (pinfunction "2_2") (pintype "passive"))
      (node (ref "R26") (pin "1") (pinfunction "1_1") (pintype "passive"))
    )
    (net (code "87") (name "Net-(J10-Pad5)") (class "Default")
      (node (ref "J10") (pin "5") (pinfunction "5_5") (pintype "passive"))
      (node (ref "R30") (pin "2") (pinfunction "2_2") (pintype "passive"))
    )
    (net (code "88") (name "Net-(J10-Pad6)") (class "Default")
      (node (ref "J10") (pin "6") (pinfunction "6_6") (pintype "passive"))
      (node (ref "R27") (pin "2") (pinfunction "2_2") (pintype "passive"))
    )
    (net (code "89") (name "Net-(J22-Pad1)") (class "Default")
      (node (ref "J22") (pin "1") (pinfunction "1_1") (pintype "passive"))
      (node (ref "R14") (pin "1") (pinfunction "1_1") (pintype "passive"))
    )
    (net (code "90") (name "Net-(J23-Pad1)") (class "Default")
      (node (ref "J23") (pin "1") (pinfunction "1_1") (pintype "passive"))
      (node (ref "R17") (pin "1") (pinfunction "1_1") (pintype "passive"))
    )
    (net (code "91") (name "Net-(LED1-A)") (class "Default")
      (node (ref "LED1") (pin "1") (pinfunction "A_1") (pintype "passive"))
      (node (ref "R7") (pin "1") (pinfunction "1_1") (pintype "passive"))
    )
    (net (code "92") (name "Net-(LED2-A)") (class "Default")
      (node (ref "LED2") (pin "1") (pinfunction "A_1") (pintype "passive"))
      (node (ref "R13") (pin "1") (pinfunction "1_1") (pintype "passive"))
    )
    (net (code "93") (name "Net-(Q1-G)") (class "Default")
      (node (ref "Q1") (pin "1") (pinfunction "G_1") (pintype "passive"))
      (node (ref "R10") (pin "1") (pinfunction "1_1") (pintype "passive"))
    )
    (net (code "94") (name "Net-(U3-BOOT)") (class "Default")
      (node (ref "C9") (pin "1") (pinfunction "1_1") (pintype "passive"))
      (node (ref "U3") (pin "1") (pinfunction "BOOT_1") (pintype "passive"))
    )
    (net (code "95") (name "Net-(U3-ENA)") (class "Default")
      (node (ref "R11") (pin "2") (pinfunction "2_2") (pintype "passive"))
      (node (ref "R3") (pin "1") (pinfunction "1_1") (pintype "passive"))
      (node (ref "U3") (pin "5") (pinfunction "ENA_5") (pintype "passive"))
    )
    (net (code "96") (name "Net-(U3-VSENSE)") (class "Default")
      (node (ref "R1") (pin "1") (pinfunction "1_1") (pintype "passive"))
      (node (ref "R8") (pin "2") (pinfunction "2_2") (pintype "passive"))
      (node (ref "U3") (pin "4") (pinfunction "VSENSE_4") (pintype "passive"))
    )
    (net (code "97") (name "Net-(U4-BOOT)") (class "Default")
      (node (ref "C10") (pin "1") (pinfunction "1_1") (pintype "passive"))
      (node (ref "U4") (pin "1") (pinfunction "BOOT_1") (pintype "passive"))
    )
    (net (code "98") (name "Net-(U4-ENA)") (class "Default")
      (node (ref "R12") (pin "2") (pinfunction "2_2") (pintype "passive"))
      (node (ref "R4") (pin "1") (pinfunction "1_1") (pintype "passive"))
      (node (ref "U4") (pin "5") (pinfunction "ENA_5") (pintype "passive"))
    )
    (net (code "99") (name "Net-(U4-VSENSE)") (class "Default")
      (node (ref "R2") (pin "1") (pinfunction "1_1") (pintype "passive"))
      (node (ref "R9") (pin "2") (pinfunction "2_2") (pintype "passive"))
      (node (ref "U4") (pin "4") (pinfunction "VSENSE_4") (pintype "passive"))
    )
    (net (code "100") (name "PG") (class "Default")
      (node (ref "C1") (pin "2") (pinfunction "2_2") (pintype "passive"))
      (node (ref "C11") (pin "2") (pinfunction "2_2") (pintype "passive"))
      (node (ref "C12") (pin "1") (pinfunction "1_1") (pintype "passive"))
      (node (ref "C13") (pin "1") (pinfunction "1_1") (pintype "passive"))
      (node (ref "C15") (pin "2") (pinfunction "2_2") (pintype "passive"))
      (node (ref "C2") (pin "1") (pinfunction "1_1") (pintype "passive"))
      (node (ref "C3") (pin "1") (pinfunction "1_1") (pintype "passive"))
      (node (ref "D3") (pin "1") (pinfunction "A_1") (pintype "passive"))
      (node (ref "J2") (pin "3") (pinfunction "3_3") (pintype "passive"))
      (node (ref "J22") (pin "3") (pinfunction "3_3") (pintype "passive"))
      (node (ref "J23") (pin "3") (pinfunction "3_3") (pintype "passive"))
      (node (ref "J5") (pin "1") (pinfunction "1_1") (pintype "passive"))
      (node (ref "J6") (pin "4") (pinfunction "4_4") (pintype "passive"))
      (node (ref "J6") (pin "5") (pinfunction "5_5") (pintype "passive"))
      (node (ref "J8") (pin "1") (pinfunction "1_1") (pintype "passive"))
      (node (ref "Q1") (pin "4") (pinfunction "D_4") (pintype "passive"))
      (node (ref "R11") (pin "1") (pinfunction "1_1") (pintype "passive"))
      (node (ref "R12") (pin "1") (pinfunction "1_1") (pintype "passive"))
      (node (ref "R6") (pin "1") (pinfunction "1_1") (pintype "passive"))
      (node (ref "R9") (pin "1") (pinfunction "1_1") (pintype "passive"))
      (node (ref "U4") (pin "6") (pinfunction "GND_6") (pintype "passive"))
      (node (ref "U4") (pin "9") (pinfunction "PowerPAD_9") (pintype "passive"))
    )
    (net (code "101") (name "VCC5V") (class "Default")
      (node (ref "C14") (pin "1") (pinfunction "1_1") (pintype "passive"))
      (node (ref "C16") (pin "1") (pinfunction "1_1") (pintype "passive"))
      (node (ref "C17") (pin "1") (pinfunction "1_1") (pintype "passive"))
      (node (ref "C21") (pin "2") (pinfunction "2_2") (pintype "passive"))
      (node (ref "C22") (pin "1") (pinfunction "1_1") (pintype "passive"))
      (node (ref "C25") (pin "1") (pinfunction "1_1") (pintype "passive"))
      (node (ref "C26") (pin "1") (pinfunction "1_1") (pintype "passive"))
      (node (ref "C4") (pin "1") (pinfunction "1_1") (pintype "passive"))
      (node (ref "C5") (pin "1") (pinfunction "1_1") (pintype "passive"))
      (node (ref "C6") (pin "1") (pinfunction "1_1") (pintype "passive"))
      (node (ref "J11") (pin "4") (pinfunction "4_4") (pintype "passive"))
      (node (ref "J12") (pin "4") (pinfunction "4_4") (pintype "passive"))
      (node (ref "J9") (pin "4") (pinfunction "4_4") (pintype "passive"))
      (node (ref "L1") (pin "1") (pinfunction "1_1") (pintype "passive"))
      (node (ref "R1") (pin "2") (pinfunction "2_2") (pintype "passive"))
      (node (ref "U1") (pin "1") (pinfunction "IN_1") (pintype "passive"))
      (node (ref "U2") (pin "1") (pinfunction "IN_1") (pintype "passive"))
      (node (ref "U5") (pin "1") (pinfunction "IN_1") (pintype "passive"))
      (node (ref "U6") (pin "5") (pinfunction "5V_5") (pintype "passive"))
      (node (ref "U6") (pin "6") (pinfunction "5V_6") (pintype "passive"))
      (node (ref "U7") (pin "3") (pinfunction "VI_3") (pintype "input"))
    )
    (net (code "102") (name "VCCBAT") (class "Default")
      (node (ref "C1") (pin "1") (pinfunction "1_1") (pintype "passive"))
      (node (ref "C11") (pin "1") (pinfunction "1_1") (pintype "passive"))
      (node (ref "C12") (pin "2") (pinfunction "2_2") (pintype "passive"))
      (node (ref "C13") (pin "2") (pinfunction "2_2") (pintype "passive"))
      (node (ref "C2") (pin "2") (pinfunction "2_2") (pintype "passive"))
      (node (ref "C3") (pin "2") (pinfunction "2_2") (pintype "passive"))
      (node (ref "J1") (pin "2") (pinfunction "2_2") (pintype "passive"))
      (node (ref "J5") (pin "2") (pinfunction "2_2") (pintype "passive"))
      (node (ref "J6") (pin "6") (pinfunction "6_6") (pintype "passive"))
      (node (ref "J6") (pin "7") (pinfunction "7_7") (pintype "passive"))
      (node (ref "J8") (pin "2") (pinfunction "2_2") (pintype "passive"))
      (node (ref "R3") (pin "2") (pinfunction "2_2") (pintype "passive"))
      (node (ref "R4") (pin "2") (pinfunction "2_2") (pintype "passive"))
      (node (ref "SW1") (pin "3") (pinfunction "3_3") (pintype "passive"))
      (node (ref "U3") (pin "7") (pinfunction "VIN_7") (pintype "passive"))
      (node (ref "U4") (pin "7") (pinfunction "VIN_7") (pintype "passive"))
    )
    (net (code "103") (name "VCCSERVO") (class "Default")
      (node (ref "C15") (pin "1") (pinfunction "1_1") (pintype "passive"))
      (node (ref "J2") (pin "2") (pinfunction "2_2") (pintype "passive"))
      (node (ref "J22") (pin "2") (pinfunction "2_2") (pintype "passive"))
      (node (ref "J23") (pin "2") (pinfunction "2_2") (pintype "passive"))
      (node (ref "L2") (pin "1") (pinfunction "1_1") (pintype "passive"))
      (node (ref "R2") (pin "2") (pinfunction "2_2") (pintype "passive"))
    )
    (net (code "104") (name "unconnected-(J13-Pad7)") (class "Default")
      (node (ref "J13") (pin "7") (pinfunction "7_7") (pintype "passive+no_connect"))
    )
    (net (code "105") (name "unconnected-(J13-Pad8)") (class "Default")
      (node (ref "J13") (pin "8") (pinfunction "8_8") (pintype "passive+no_connect"))
    )
    (net (code "106") (name "unconnected-(J14-Pad5)") (class "Default")
      (node (ref "J14") (pin "5") (pinfunction "5_5") (pintype "passive+no_connect"))
    )
    (net (code "107") (name "unconnected-(J14-Pad6)") (class "Default")
      (node (ref "J14") (pin "6") (pinfunction "6_6") (pintype "passive+no_connect"))
    )
    (net (code "108") (name "unconnected-(J15-Pad5)") (class "Default")
      (node (ref "J15") (pin "5") (pinfunction "5_5") (pintype "passive+no_connect"))
    )
    (net (code "109") (name "unconnected-(J15-Pad6)") (class "Default")
      (node (ref "J15") (pin "6") (pinfunction "6_6") (pintype "passive+no_connect"))
    )
    (net (code "110") (name "unconnected-(J16-Pad5)") (class "Default")
      (node (ref "J16") (pin "5") (pinfunction "5_5") (pintype "passive+no_connect"))
    )
    (net (code "111") (name "unconnected-(J16-Pad6)") (class "Default")
      (node (ref "J16") (pin "6") (pinfunction "6_6") (pintype "passive+no_connect"))
    )
    (net (code "112") (name "unconnected-(J17-Pad5)") (class "Default")
      (node (ref "J17") (pin "5") (pinfunction "5_5") (pintype "passive+no_connect"))
    )
    (net (code "113") (name "unconnected-(J17-Pad6)") (class "Default")
      (node (ref "J17") (pin "6") (pinfunction "6_6") (pintype "passive+no_connect"))
    )
    (net (code "114") (name "unconnected-(SW1-Pad1)") (class "Default")
      (node (ref "SW1") (pin "1") (pinfunction "1_1") (pintype "passive"))
    )
    (net (code "115") (name "unconnected-(U1-NC-Pad4)") (class "Default")
      (node (ref "U1") (pin "4") (pinfunction "NC_4") (pintype "passive+no_connect"))
    )
    (net (code "116") (name "unconnected-(U2-NC-Pad4)") (class "Default")
      (node (ref "U2") (pin "4") (pinfunction "NC_4") (pintype "passive+no_connect"))
    )
    (net (code "117") (name "unconnected-(U3-NC-Pad2)") (class "Default")
      (node (ref "U3") (pin "2") (pinfunction "NC_2") (pintype "passive+no_connect"))
    )
    (net (code "118") (name "unconnected-(U3-NC-Pad3)") (class "Default")
      (node (ref "U3") (pin "3") (pinfunction "NC_3") (pintype "passive+no_connect"))
    )
    (net (code "119") (name "unconnected-(U4-NC-Pad2)") (class "Default")
      (node (ref "U4") (pin "2") (pinfunction "NC_2") (pintype "passive+no_connect"))
    )
    (net (code "120") (name "unconnected-(U4-NC-Pad3)") (class "Default")
      (node (ref "U4") (pin "3") (pinfunction "NC_3") (pintype "passive+no_connect"))
    )
    (net (code "121") (name "unconnected-(U5-NC-Pad4)") (class "Default")
      (node (ref "U5") (pin "4") (pinfunction "NC_4") (pintype "passive+no_connect"))
    )
    (net (code "122") (name "unconnected-(U6-2DN-Pad22)") (class "Default")
      (node (ref "U6") (pin "22") (pinfunction "2DN_22") (pintype "passive+no_connect"))
    )
    (net (code "123") (name "unconnected-(U6-2DP-Pad21)") (class "Default")
      (node (ref "U6") (pin "21") (pinfunction "2DP_21") (pintype "passive+no_connect"))
    )
    (net (code "124") (name "unconnected-(U6-3V3-Pad3)") (class "Default")
      (node (ref "U6") (pin "3") (pinfunction "3V3_3") (pintype "passive+no_connect"))
    )
    (net (code "125") (name "unconnected-(U6-3V3-Pad4)") (class "Default")
      (node (ref "U6") (pin "4") (pinfunction "3V3_4") (pintype "passive+no_connect"))
    )
    (net (code "126") (name "unconnected-(U6-B9-Pad49)") (class "Default")
      (node (ref "U6") (pin "49") (pinfunction "B9_49") (pintype "passive+no_connect"))
    )
    (net (code "127") (name "unconnected-(U6-B14-Pad30)") (class "Default")
      (node (ref "U6") (pin "30") (pinfunction "B14_30") (pintype "passive+no_connect"))
    )
    (net (code "128") (name "unconnected-(U6-B15-Pad28)") (class "Default")
      (node (ref "U6") (pin "28") (pinfunction "B15_28") (pintype "passive+no_connect"))
    )
    (net (code "129") (name "unconnected-(U6-B21-Pad35)") (class "Default")
      (node (ref "U6") (pin "35") (pinfunction "B21_35") (pintype "passive+no_connect"))
    )
    (net (code "130") (name "unconnected-(U6-OF-Pad7)") (class "Default")
      (node (ref "U6") (pin "7") (pinfunction "OF_7") (pintype "passive+no_connect"))
    )
    (net (code "131") (name "unconnected-(U6-WU-Pad8)") (class "Default")
      (node (ref "U6") (pin "8") (pinfunction "WU_8") (pintype "passive+no_connect"))
    )
  )
)
